# Hpowerv2.net
KiCad netlist of a schematic drawn in Altium Designer
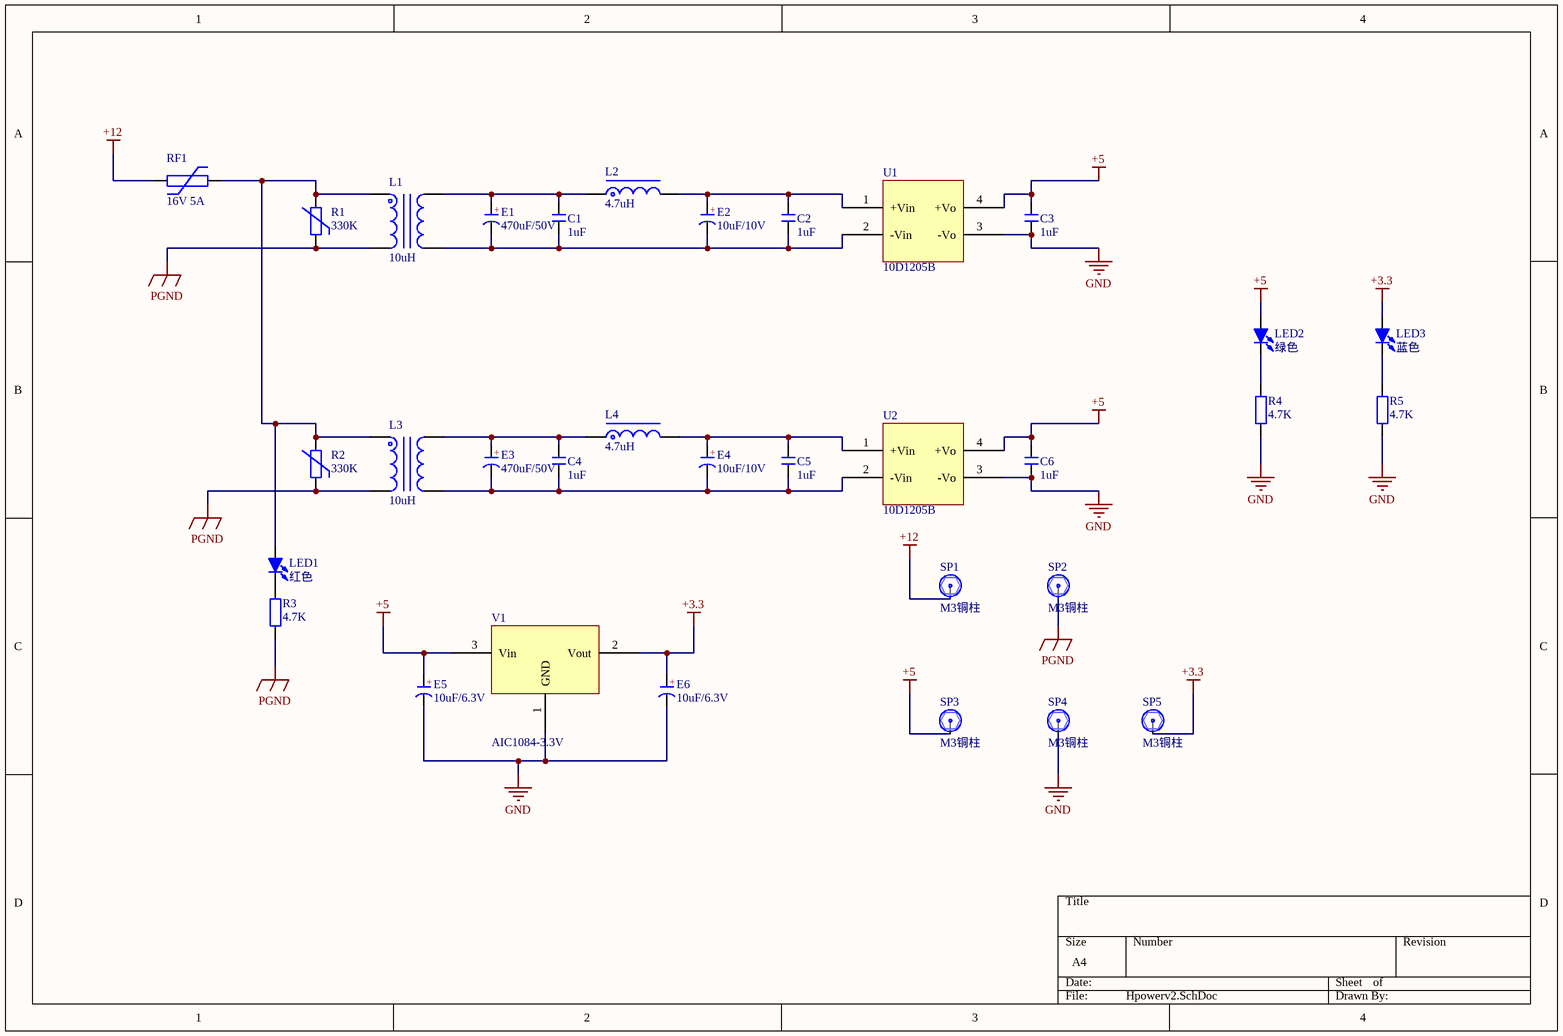
[diagram p0: Hpowerv2.SchDoc]

(export (version "E")
  (design (tool "Eeschema 10.0.6"))
  (components
    (comp (ref "C1")
      (value "1uF")
      (footprint "CC 2.2*5")
      (description "直插瓷片电容")
      (fields (field (name "版权归属") "源创客"))
      (libsource (lib "3.1   - 电阻-电容-电感") (part "C-CC"))
    )
    (comp (ref "C2")
      (value "1uF")
      (footprint "CC 2.2*5")
      (description "直插瓷片电容")
      (fields (field (name "版权归属") "源创客"))
      (libsource (lib "3.1   - 电阻-电容-电感") (part "C-CC"))
    )
    (comp (ref "C3")
      (value "1uF")
      (footprint "CC 2.2*5")
      (description "直插瓷片电容")
      (fields (field (name "版权归属") "源创客"))
      (libsource (lib "3.1   - 电阻-电容-电感") (part "C-CC"))
    )
    (comp (ref "C4")
      (value "1uF")
      (footprint "CC 2.2*5")
      (description "直插瓷片电容")
      (fields (field (name "版权归属") "源创客"))
      (libsource (lib "3.1   - 电阻-电容-电感") (part "C-CC"))
    )
    (comp (ref "C5")
      (value "1uF")
      (footprint "CC 2.2*5")
      (description "直插瓷片电容")
      (fields (field (name "版权归属") "源创客"))
      (libsource (lib "3.1   - 电阻-电容-电感") (part "C-CC"))
    )
    (comp (ref "C6")
      (value "1uF")
      (footprint "CC 2.2*5")
      (description "直插瓷片电容")
      (fields (field (name "版权归属") "源创客"))
      (libsource (lib "3.1   - 电阻-电容-电感") (part "C-CC"))
    )
    (comp (ref "E1")
      (value "470uF/50V")
      (footprint "CM G(12.5*13.5)")
      (description "贴片电解电容")
      (fields (field (name "版权归属") "源创客"))
      (libsource (lib "3.1   - 电阻-电容-电感") (part "C-CM"))
    )
    (comp (ref "E2")
      (value "10uF/10V")
      (footprint "CM G(12.5*13.5)")
      (description "贴片电解电容")
      (fields (field (name "版权归属") "源创客"))
      (libsource (lib "3.1   - 电阻-电容-电感") (part "C-CM"))
    )
    (comp (ref "E3")
      (value "470uF/50V")
      (footprint "CM G(12.5*13.5)")
      (description "贴片电解电容")
      (fields (field (name "版权归属") "源创客"))
      (libsource (lib "3.1   - 电阻-电容-电感") (part "C-CM"))
    )
    (comp (ref "E4")
      (value "10uF/10V")
      (footprint "CM G(12.5*13.5)")
      (description "贴片电解电容")
      (fields (field (name "版权归属") "源创客"))
      (libsource (lib "3.1   - 电阻-电容-电感") (part "C-CM"))
    )
    (comp (ref "E5")
      (value "10uF/6.3V")
      (footprint "CD A(3216)")
      (description "贴片钽电容")
      (fields (field (name "版权归属") "源创客"))
      (libsource (lib "3.1   - 电阻-电容-电感") (part "C-CD"))
    )
    (comp (ref "E6")
      (value "10uF/6.3V")
      (footprint "CD A(3216)")
      (description "贴片钽电容")
      (fields (field (name "版权归属") "源创客"))
      (libsource (lib "3.1   - 电阻-电容-电感") (part "C-CD"))
    )
    (comp (ref "L1")
      (value "10uH")
      (footprint "UU9.8")
      (description "共模电感")
      (fields (field (name "版权归属") "源创客"))
      (libsource (lib "3.1   - 电阻-电容-电感") (part "L-CMC"))
    )
    (comp (ref "L2")
      (value "4.7uH")
      (footprint "NR5020")
      (description "NR磁胶电感")
      (fields (field (name "版权归属") "源创客"))
      (libsource (lib "3.1   - 电阻-电容-电感") (part "L-NR"))
    )
    (comp (ref "L3")
      (value "10uH")
      (footprint "UU9.8")
      (description "共模电感")
      (fields (field (name "版权归属") "源创客"))
      (libsource (lib "3.1   - 电阻-电容-电感") (part "L-CMC"))
    )
    (comp (ref "L4")
      (value "4.7uH")
      (footprint "NR5020")
      (description "NR磁胶电感")
      (fields (field (name "版权归属") "源创客"))
      (libsource (lib "3.1   - 电阻-电容-电感") (part "L-NR"))
    )
    (comp (ref "LED1")
      (value "红色")
      (footprint "LED 0603R")
      (description "贴片LED")
      (fields (field (name "版权归属") "源创客"))
      (libsource (lib "9.1   - LED") (part "LED-SMD"))
    )
    (comp (ref "LED2")
      (value "绿色")
      (footprint "LED 0603G")
      (description "贴片LED")
      (fields (field (name "版权归属") "源创客"))
      (libsource (lib "9.1   - LED") (part "LED-SMD"))
    )
    (comp (ref "LED3")
      (value "蓝色")
      (footprint "LED 0603B")
      (description "贴片LED")
      (fields (field (name "版权归属") "源创客"))
      (libsource (lib "9.1   - LED") (part "LED-SMD"))
    )
    (comp (ref "R1")
      (value "330K")
      (footprint "14D")
      (description "压敏电阻")
      (fields (field (name "版权归属") "源创客"))
      (libsource (lib "3.1   - 电阻-电容-电感") (part "R_VDR"))
    )
    (comp (ref "R2")
      (value "330K")
      (footprint "14D")
      (description "压敏电阻")
      (fields (field (name "版权归属") "源创客"))
      (libsource (lib "3.1   - 电阻-电容-电感") (part "R_VDR"))
    )
    (comp (ref "R3")
      (value "4.7K")
      (footprint "R 0603_M")
      (description "贴片电阻")
      (fields (field (name "版权归属") "源创客"))
      (libsource (lib "3.1   - 电阻-电容-电感") (part "R"))
    )
    (comp (ref "R4")
      (value "4.7K")
      (footprint "R 0603_M")
      (description "贴片电阻")
      (fields (field (name "版权归属") "源创客"))
      (libsource (lib "3.1   - 电阻-电容-电感") (part "R"))
    )
    (comp (ref "R5")
      (value "4.7K")
      (footprint "R 0603_M")
      (description "贴片电阻")
      (fields (field (name "版权归属") "源创客"))
      (libsource (lib "3.1   - 电阻-电容-电感") (part "R"))
    )
    (comp (ref "RF1")
      (value "16V 5A")
      (footprint "14D")
      (description "PPTC自恢复保险丝")
      (fields (field (name "版权归属") "源创客"))
      (libsource (lib "10.1 - 保险丝-晶振") (part "PPTC"))
    )
    (comp (ref "SP1")
      (value "M3铜柱")
      (footprint "M3x14_N")
      (description "铜柱")
      (fields (field (name "版权归属") "源创客"))
      (libsource (lib "15.1 - 未分类器件") (part "铜柱大焊盘"))
    )
    (comp (ref "SP2")
      (value "M3铜柱")
      (footprint "M3x14_N")
      (description "铜柱")
      (fields (field (name "版权归属") "源创客"))
      (libsource (lib "15.1 - 未分类器件") (part "铜柱大焊盘"))
    )
    (comp (ref "SP3")
      (value "M3铜柱")
      (footprint "M3x14_N")
      (description "铜柱")
      (fields (field (name "版权归属") "源创客"))
      (libsource (lib "15.1 - 未分类器件") (part "铜柱大焊盘"))
    )
    (comp (ref "SP4")
      (value "M3铜柱")
      (footprint "M3x14_N")
      (description "铜柱")
      (fields (field (name "版权归属") "源创客"))
      (libsource (lib "15.1 - 未分类器件") (part "铜柱大焊盘"))
    )
    (comp (ref "SP5")
      (value "M3铜柱")
      (footprint "M3x14_N")
      (description "铜柱")
      (fields (field (name "版权归属") "源创客"))
      (libsource (lib "15.1 - 未分类器件") (part "铜柱大焊盘"))
    )
    (comp (ref "U1")
      (value "10D1205B")
      (footprint "10D12B-10WDCDC")
      (description "DC-DC 12V转5V隔离降压模块")
      (libsource (lib "HLKPower") (part "10D1205B"))
    )
    (comp (ref "U2")
      (value "10D1205B")
      (footprint "10D12B-10WDCDC")
      (description "DC-DC 12V转5V隔离降压模块")
      (libsource (lib "HLKPower") (part "10D1205B"))
    )
    (comp (ref "V1")
      (value "AIC1084-3.3V")
      (footprint "TO263-3B")
      (description "大功率LDO")
      (libsource (lib "1.3   - 电源类芯片") (part "AIC1084"))
    )
  )
  (nets
    (net (code "1") (name "+3.3") (class "Default")
      (node (ref "E6") (pin "1") (pinfunction "A_1") (pintype "passive"))
      (node (ref "LED3") (pin "1") (pinfunction "A_1") (pintype "passive"))
      (node (ref "SP5") (pin "1") (pinfunction "1_1") (pintype "passive"))
      (node (ref "V1") (pin "2") (pinfunction "Vout_2") (pintype "passive"))
    )
    (net (code "2") (name "+5") (class "Default")
      (node (ref "C3") (pin "1") (pinfunction "1_1") (pintype "passive"))
      (node (ref "C6") (pin "1") (pinfunction "1_1") (pintype "passive"))
      (node (ref "E5") (pin "1") (pinfunction "A_1") (pintype "passive"))
      (node (ref "LED2") (pin "1") (pinfunction "A_1") (pintype "passive"))
      (node (ref "SP3") (pin "1") (pinfunction "1_1") (pintype "passive"))
      (node (ref "U1") (pin "4") (pinfunction "+Vo_4") (pintype "passive"))
      (node (ref "U2") (pin "4") (pinfunction "+Vo_4") (pintype "passive"))
      (node (ref "V1") (pin "3") (pinfunction "Vin_3") (pintype "passive"))
    )
    (net (code "3") (name "+12") (class "Default")
      (node (ref "RF1") (pin "1") (pinfunction "1_1") (pintype "passive"))
      (node (ref "SP1") (pin "1") (pinfunction "1_1") (pintype "passive"))
    )
    (net (code "4") (name "GND") (class "Default")
      (node (ref "C3") (pin "2") (pinfunction "2_2") (pintype "passive"))
      (node (ref "C6") (pin "2") (pinfunction "2_2") (pintype "passive"))
      (node (ref "E5") (pin "2") (pinfunction "K_2") (pintype "passive"))
      (node (ref "E6") (pin "2") (pinfunction "K_2") (pintype "passive"))
      (node (ref "R4") (pin "1") (pinfunction "1_1") (pintype "passive"))
      (node (ref "R5") (pin "1") (pinfunction "1_1") (pintype "passive"))
      (node (ref "SP4") (pin "1") (pinfunction "1_1") (pintype "passive"))
      (node (ref "U1") (pin "3") (pinfunction "-Vo_3") (pintype "passive"))
      (node (ref "U2") (pin "3") (pinfunction "-Vo_3") (pintype "passive"))
      (node (ref "V1") (pin "1") (pinfunction "GND_1") (pintype "passive"))
    )
    (net (code "5") (name "Net-(E1-A)") (class "Default")
      (node (ref "C1") (pin "1") (pinfunction "1_1") (pintype "passive"))
      (node (ref "E1") (pin "1") (pinfunction "A_1") (pintype "passive"))
      (node (ref "L1") (pin "4") (pinfunction "4_4") (pintype "passive"))
      (node (ref "L2") (pin "1") (pinfunction "1_1") (pintype "passive"))
    )
    (net (code "6") (name "Net-(E1-K)") (class "Default")
      (node (ref "C1") (pin "2") (pinfunction "2_2") (pintype "passive"))
      (node (ref "C2") (pin "2") (pinfunction "2_2") (pintype "passive"))
      (node (ref "E1") (pin "2") (pinfunction "K_2") (pintype "passive"))
      (node (ref "E2") (pin "2") (pinfunction "K_2") (pintype "passive"))
      (node (ref "L1") (pin "3") (pinfunction "3_3") (pintype "passive"))
      (node (ref "U1") (pin "2") (pinfunction "-Vin_2") (pintype "passive"))
    )
    (net (code "7") (name "Net-(E2-A)") (class "Default")
      (node (ref "C2") (pin "1") (pinfunction "1_1") (pintype "passive"))
      (node (ref "E2") (pin "1") (pinfunction "A_1") (pintype "passive"))
      (node (ref "L2") (pin "2") (pinfunction "2_2") (pintype "passive"))
      (node (ref "U1") (pin "1") (pinfunction "+Vin_1") (pintype "passive"))
    )
    (net (code "8") (name "Net-(E3-A)") (class "Default")
      (node (ref "C4") (pin "1") (pinfunction "1_1") (pintype "passive"))
      (node (ref "E3") (pin "1") (pinfunction "A_1") (pintype "passive"))
      (node (ref "L3") (pin "4") (pinfunction "4_4") (pintype "passive"))
      (node (ref "L4") (pin "1") (pinfunction "1_1") (pintype "passive"))
    )
    (net (code "9") (name "Net-(E3-K)") (class "Default")
      (node (ref "C4") (pin "2") (pinfunction "2_2") (pintype "passive"))
      (node (ref "C5") (pin "2") (pinfunction "2_2") (pintype "passive"))
      (node (ref "E3") (pin "2") (pinfunction "K_2") (pintype "passive"))
      (node (ref "E4") (pin "2") (pinfunction "K_2") (pintype "passive"))
      (node (ref "L3") (pin "3") (pinfunction "3_3") (pintype "passive"))
      (node (ref "U2") (pin "2") (pinfunction "-Vin_2") (pintype "passive"))
    )
    (net (code "10") (name "Net-(E4-A)") (class "Default")
      (node (ref "C5") (pin "1") (pinfunction "1_1") (pintype "passive"))
      (node (ref "E4") (pin "1") (pinfunction "A_1") (pintype "passive"))
      (node (ref "L4") (pin "2") (pinfunction "2_2") (pintype "passive"))
      (node (ref "U2") (pin "1") (pinfunction "+Vin_1") (pintype "passive"))
    )
    (net (code "11") (name "Net-(LED1-A)") (class "Default")
      (node (ref "L1") (pin "1") (pinfunction "1_1") (pintype "passive"))
      (node (ref "L3") (pin "1") (pinfunction "1_1") (pintype "passive"))
      (node (ref "LED1") (pin "1") (pinfunction "A_1") (pintype "passive"))
      (node (ref "R1") (pin "2") (pinfunction "2_2") (pintype "passive"))
      (node (ref "R2") (pin "2") (pinfunction "2_2") (pintype "passive"))
      (node (ref "RF1") (pin "2") (pinfunction "2_2") (pintype "passive"))
    )
    (net (code "12") (name "Net-(LED1-K)") (class "Default")
      (node (ref "LED1") (pin "2") (pinfunction "K_2") (pintype "passive"))
      (node (ref "R3") (pin "2") (pinfunction "2_2") (pintype "passive"))
    )
    (net (code "13") (name "Net-(LED2-K)") (class "Default")
      (node (ref "LED2") (pin "2") (pinfunction "K_2") (pintype "passive"))
      (node (ref "R4") (pin "2") (pinfunction "2_2") (pintype "passive"))
    )
    (net (code "14") (name "Net-(LED3-K)") (class "Default")
      (node (ref "LED3") (pin "2") (pinfunction "K_2") (pintype "passive"))
      (node (ref "R5") (pin "2") (pinfunction "2_2") (pintype "passive"))
    )
    (net (code "15") (name "PGND") (class "Default")
      (node (ref "L1") (pin "2") (pinfunction "2_2") (pintype "passive"))
      (node (ref "L3") (pin "2") (pinfunction "2_2") (pintype "passive"))
      (node (ref "R1") (pin "1") (pinfunction "1_1") (pintype "passive"))
      (node (ref "R2") (pin "1") (pinfunction "1_1") (pintype "passive"))
      (node (ref "R3") (pin "1") (pinfunction "1_1") (pintype "passive"))
      (node (ref "SP2") (pin "1") (pinfunction "1_1") (pintype "passive"))
    )
  )
)
